# COMM.net
KiCad netlist of a schematic drawn in Altium Designer
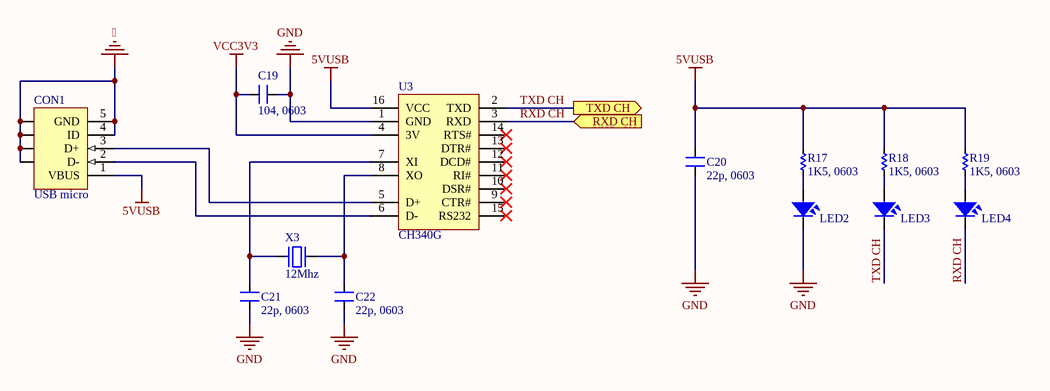
[diagram p0: COMM.SchDoc]

(export (version "E")
  (design (tool "Eeschema 10.0.6"))
  (components
    (comp (ref "C19")
      (value "104, 0603")
      (footprint "SM-0603")
      (description "Cap SMD")
      (libsource (lib "KhanhBK_Library_4") (part "CM"))
    )
    (comp (ref "C20")
      (value "22p, 0603")
      (footprint "SM-0603")
      (description "Cap SMD")
      (libsource (lib "KhanhBK_Library_4") (part "CM"))
    )
    (comp (ref "C21")
      (value "22p, 0603")
      (footprint "SM-0603")
      (description "Cap SMD")
      (libsource (lib "KhanhBK_Library_4") (part "CM"))
    )
    (comp (ref "C22")
      (value "22p, 0603")
      (footprint "SM-0603")
      (description "Cap SMD")
      (libsource (lib "KhanhBK_Library_4") (part "CM"))
    )
    (comp (ref "CON1")
      (value "USB micro")
      (footprint "CONN/USB/MICRO/RA")
      (description "USB micro, 5 pins")
      (libsource (lib "connectors") (part "CON USB micro"))
    )
    (comp (ref "LED2")
      (value "LED")
      (footprint "LED-0805-Blue")
      (libsource (lib "KhanhBK_SCH_Library_1") (part "LED SMD"))
    )
    (comp (ref "LED3")
      (value "LED")
      (footprint "LED-0805-Blue")
      (libsource (lib "KhanhBK_SCH_Library_1") (part "LED SMD"))
    )
    (comp (ref "LED4")
      (value "LED")
      (footprint "LED-0805-Blue")
      (libsource (lib "KhanhBK_SCH_Library_1") (part "LED SMD"))
    )
    (comp (ref "R17")
      (value "1K5, 0603")
      (footprint "RES-SMD-0603")
      (description "Resistor")
      (fields
        (field (name "MANUFACTURER") "Generic Components")
        (field (name "PUBLISHER") "Altium Hobart Technology Centre")
      )
      (libsource (lib "KhanhBK_SCH_Library_1") (part "Res-SMD"))
    )
    (comp (ref "R18")
      (value "1K5, 0603")
      (footprint "RES-SMD-0603")
      (description "Resistor")
      (fields
        (field (name "MANUFACTURER") "Generic Components")
        (field (name "PUBLISHER") "Altium Hobart Technology Centre")
      )
      (libsource (lib "KhanhBK_SCH_Library_1") (part "Res-SMD"))
    )
    (comp (ref "R19")
      (value "1K5, 0603")
      (footprint "RES-SMD-0603")
      (description "Resistor")
      (fields
        (field (name "MANUFACTURER") "Generic Components")
        (field (name "PUBLISHER") "Altium Hobart Technology Centre")
      )
      (libsource (lib "KhanhBK_SCH_Library_1") (part "Res-SMD"))
    )
    (comp (ref "U3")
      (value "CH340G")
      (footprint "SO16")
      (description "High and Low Side Driver")
      (fields (field (name "PUBLISHER") "Altium Limited"))
      (libsource (lib "KhanhBK_SCH_Library_1") (part "CH340G"))
    )
    (comp (ref "X3")
      (value "12Mhz")
      (footprint "XT2")
      (description "Crystal, 32.768 KHz, -40 to 85 degC, 3.2 x 1.5 x 0.9 mm SMD")
      (libsource (lib "KhanhBK_SCH_Library_1") (part "XT2"))
    )
  )
  (nets
    (net (code "1") (name "") (class "Default")
      (node (ref "CON1") (pin "4") (pinfunction "ID_4") (pintype "passive"))
      (node (ref "CON1") (pin "5") (pinfunction "GND_5") (pintype "power_in"))
      (node (ref "CON1") (pin "6") (pinfunction "SHLD_6") (pintype "passive"))
      (node (ref "CON1") (pin "7") (pinfunction "SHLD_7") (pintype "passive"))
      (node (ref "CON1") (pin "8") (pinfunction "SHLD_8") (pintype "passive"))
      (node (ref "CON1") (pin "9") (pinfunction "SHLD_9") (pintype "passive"))
    )
    (net (code "2") (name "/RXD CH") (class "Default")
      (node (ref "LED4") (pin "2") (pinfunction "2_2") (pintype "passive"))
      (node (ref "U3") (pin "3") (pinfunction "RXD_3") (pintype "passive"))
    )
    (net (code "3") (name "/TXD CH") (class "Default")
      (node (ref "LED3") (pin "2") (pinfunction "2_2") (pintype "passive"))
      (node (ref "U3") (pin "2") (pinfunction "TXD_2") (pintype "passive"))
    )
    (net (code "4") (name "5VUSB") (class "Default")
      (node (ref "C20") (pin "2") (pinfunction "2_2") (pintype "passive"))
      (node (ref "CON1") (pin "1") (pinfunction "VBUS_1") (pintype "power_in"))
      (node (ref "R17") (pin "1") (pinfunction "1_1") (pintype "passive"))
      (node (ref "R18") (pin "1") (pinfunction "1_1") (pintype "passive"))
      (node (ref "R19") (pin "1") (pinfunction "1_1") (pintype "passive"))
      (node (ref "U3") (pin "16") (pinfunction "VCC_16") (pintype "passive"))
    )
    (net (code "5") (name "GND") (class "Default")
      (node (ref "C19") (pin "1") (pinfunction "1_1") (pintype "passive"))
      (node (ref "C20") (pin "1") (pinfunction "1_1") (pintype "passive"))
      (node (ref "C21") (pin "1") (pinfunction "1_1") (pintype "passive"))
      (node (ref "C22") (pin "1") (pinfunction "1_1") (pintype "passive"))
      (node (ref "LED2") (pin "2") (pinfunction "2_2") (pintype "passive"))
      (node (ref "U3") (pin "1") (pinfunction "GND_1") (pintype "passive"))
    )
    (net (code "6") (name "Net-(CON1-D+)") (class "Default")
      (node (ref "CON1") (pin "3") (pinfunction "D+_3") (pintype "input"))
      (node (ref "U3") (pin "5") (pinfunction "D+_5") (pintype "passive"))
    )
    (net (code "7") (name "Net-(CON1-D-)") (class "Default")
      (node (ref "CON1") (pin "2") (pinfunction "D-_2") (pintype "input"))
      (node (ref "U3") (pin "6") (pinfunction "D-_6") (pintype "passive"))
    )
    (net (code "8") (name "Net-(LED2-Pad1)") (class "Default")
      (node (ref "LED2") (pin "1") (pinfunction "1_1") (pintype "passive"))
      (node (ref "R17") (pin "2") (pinfunction "2_2") (pintype "passive"))
    )
    (net (code "9") (name "Net-(LED3-Pad1)") (class "Default")
      (node (ref "LED3") (pin "1") (pinfunction "1_1") (pintype "passive"))
      (node (ref "R18") (pin "2") (pinfunction "2_2") (pintype "passive"))
    )
    (net (code "10") (name "Net-(LED4-Pad1)") (class "Default")
      (node (ref "LED4") (pin "1") (pinfunction "1_1") (pintype "passive"))
      (node (ref "R19") (pin "2") (pinfunction "2_2") (pintype "passive"))
    )
    (net (code "11") (name "Net-(U3-XI)") (class "Default")
      (node (ref "C21") (pin "2") (pinfunction "2_2") (pintype "passive"))
      (node (ref "U3") (pin "7") (pinfunction "XI_7") (pintype "passive"))
      (node (ref "X3") (pin "1") (pinfunction "1_1") (pintype "passive"))
    )
    (net (code "12") (name "Net-(U3-XO)") (class "Default")
      (node (ref "C22") (pin "2") (pinfunction "2_2") (pintype "passive"))
      (node (ref "U3") (pin "8") (pinfunction "XO_8") (pintype "passive"))
      (node (ref "X3") (pin "2") (pinfunction "2_2") (pintype "passive"))
    )
    (net (code "13") (name "VCC3V3") (class "Default")
      (node (ref "C19") (pin "2") (pinfunction "2_2") (pintype "passive"))
      (node (ref "U3") (pin "4") (pinfunction "3V_4") (pintype "passive"))
    )
    (net (code "14") (name "unconnected-(U3-CTR#-Pad9)") (class "Default")
      (node (ref "U3") (pin "9") (pinfunction "CTR#_9") (pintype "passive+no_connect"))
    )
    (net (code "15") (name "unconnected-(U3-DCD#-Pad12)") (class "Default")
      (node (ref "U3") (pin "12") (pinfunction "DCD#_12") (pintype "passive+no_connect"))
    )
    (net (code "16") (name "unconnected-(U3-DSR#-Pad10)") (class "Default")
      (node (ref "U3") (pin "10") (pinfunction "DSR#_10") (pintype "passive+no_connect"))
    )
    (net (code "17") (name "unconnected-(U3-DTR#-Pad13)") (class "Default")
      (node (ref "U3") (pin "13") (pinfunction "DTR#_13") (pintype "passive+no_connect"))
    )
    (net (code "18") (name "unconnected-(U3-RI#-Pad11)") (class "Default")
      (node (ref "U3") (pin "11") (pinfunction "RI#_11") (pintype "passive+no_connect"))
    )
    (net (code "19") (name "unconnected-(U3-RS232-Pad15)") (class "Default")
      (node (ref "U3") (pin "15") (pinfunction "RS232_15") (pintype "passive+no_connect"))
    )
    (net (code "20") (name "unconnected-(U3-RTS#-Pad14)") (class "Default")
      (node (ref "U3") (pin "14") (pinfunction "RTS#_14") (pintype "passive+no_connect"))
    )
  )
)
